# trashotron-driver.net
KiCad netlist of a schematic drawn in EAGLE
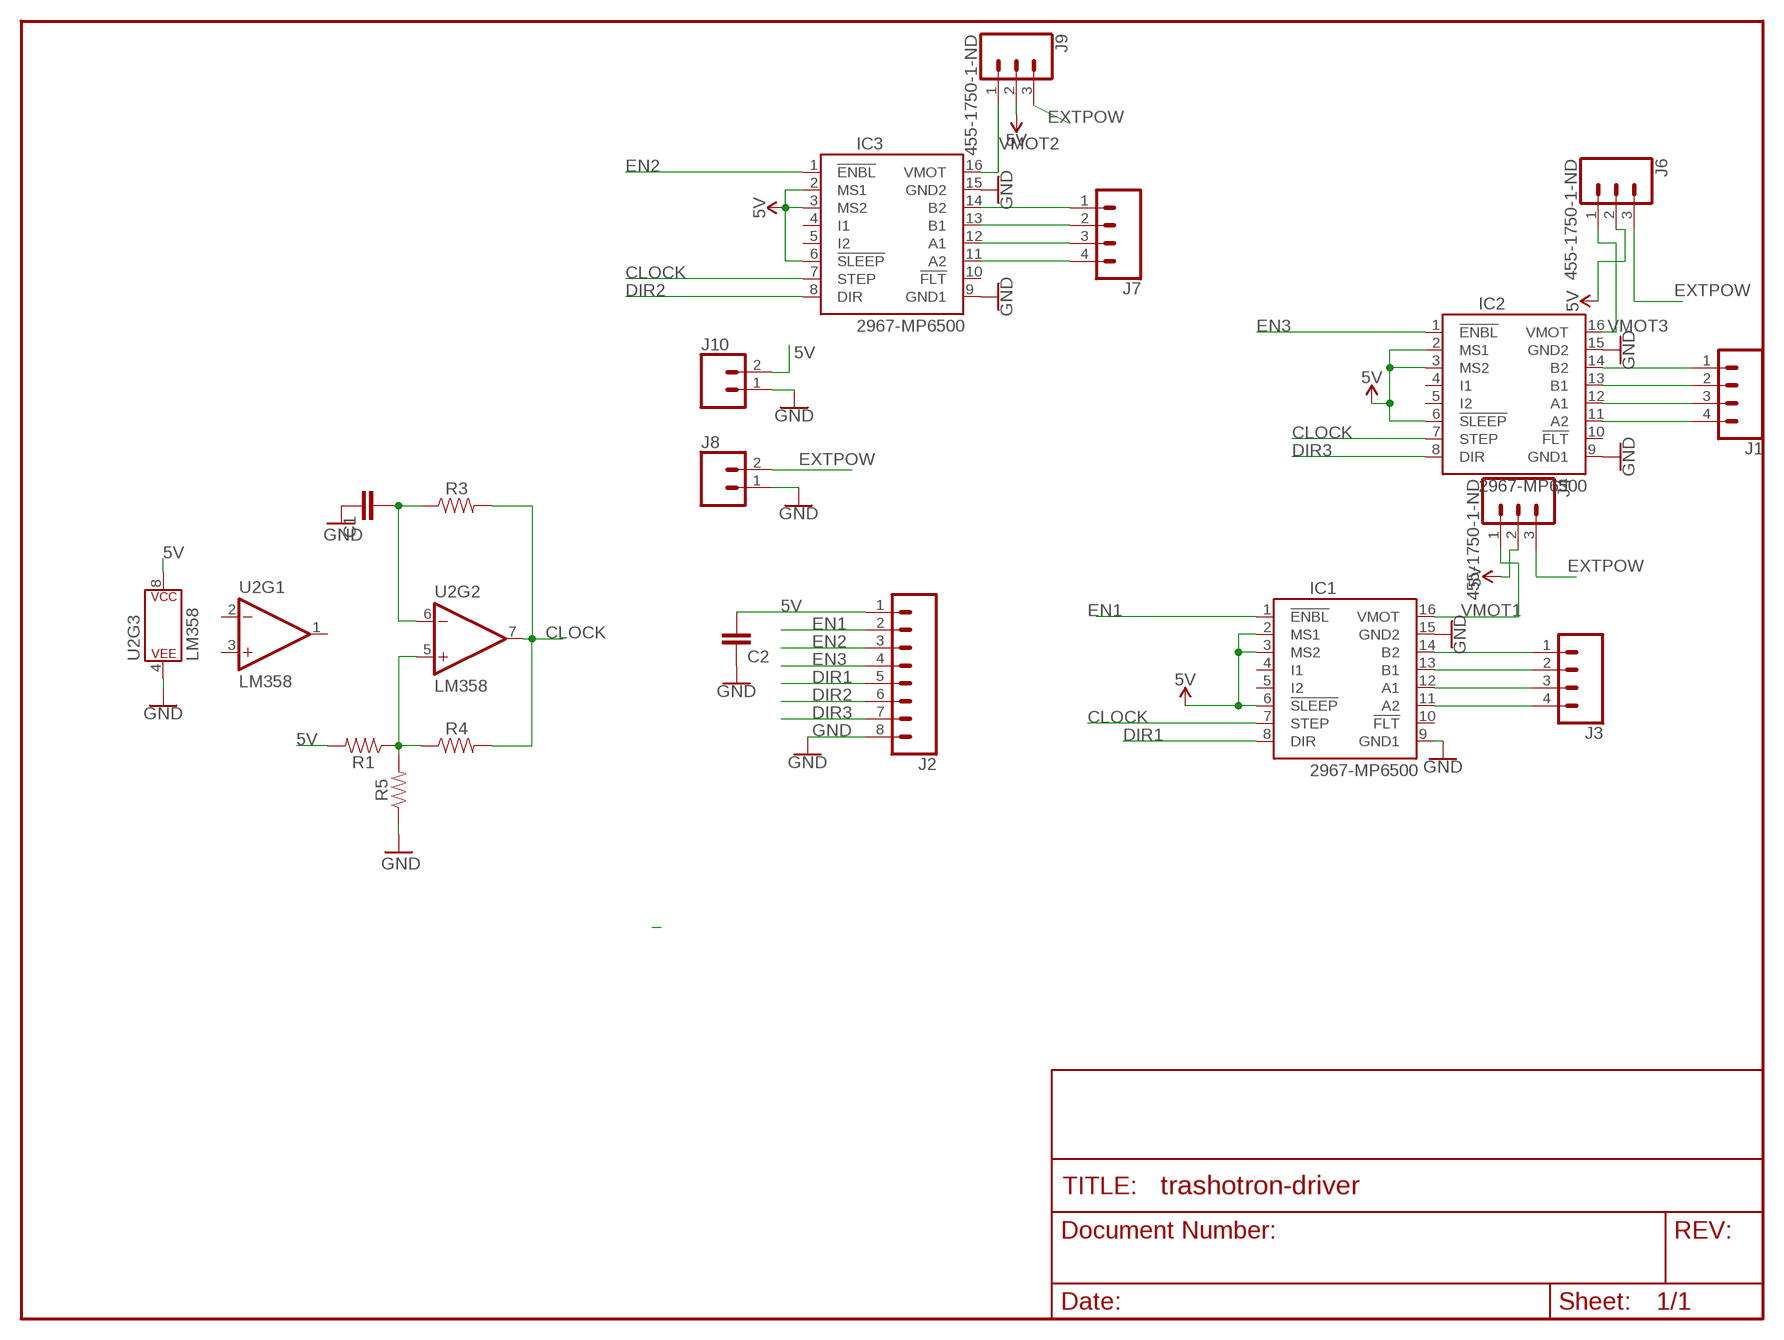
[diagram p0: schematic, sheet 1]

(export (version "E")
  (design (tool "Eeschema 10.0.6"))
  (components
    (comp (ref "C1")
      (value "C-EU050-050X075")
      (footprint "eagle-import:C050-050X075")
      (libsource (lib "eagle-import") (part "C-EU050-050X075"))
    )
    (comp (ref "C2")
      (value "C-EU050-050X075")
      (footprint "eagle-import:C050-050X075")
      (libsource (lib "eagle-import") (part "C-EU050-050X075"))
    )
    (comp (ref "IC1")
      (value "2967-MP6500")
      (footprint "eagle-import:MP6500")
      (libsource (lib "eagle-import") (part "2967-MP6500"))
    )
    (comp (ref "IC2")
      (value "2967-MP6500")
      (footprint "eagle-import:MP6500")
      (libsource (lib "eagle-import") (part "2967-MP6500"))
    )
    (comp (ref "IC3")
      (value "2967-MP6500")
      (footprint "eagle-import:MP6500")
      (libsource (lib "eagle-import") (part "2967-MP6500"))
    )
    (comp (ref "J1")
      (value "CONN_04")
      (footprint "eagle-import:1X04")
      (libsource (lib "eagle-import") (part "CONN_04"))
    )
    (comp (ref "J2")
      (value "CONN_08\"")
      (footprint "eagle-import:1X08")
      (libsource (lib "eagle-import") (part "CONN_08{dblquote}"))
    )
    (comp (ref "J3")
      (value "CONN_04")
      (footprint "eagle-import:1X04")
      (libsource (lib "eagle-import") (part "CONN_04"))
    )
    (comp (ref "J4")
      (value "455-1750-1-ND")
      (footprint "eagle-import:1X03")
      (libsource (lib "eagle-import") (part "CONN_03"))
    )
    (comp (ref "J6")
      (value "455-1750-1-ND")
      (footprint "eagle-import:1X03")
      (libsource (lib "eagle-import") (part "CONN_03"))
    )
    (comp (ref "J7")
      (value "CONN_04")
      (footprint "eagle-import:1X04")
      (libsource (lib "eagle-import") (part "CONN_04"))
    )
    (comp (ref "J8")
      (value "CONN_02")
      (footprint "eagle-import:1X02")
      (libsource (lib "eagle-import") (part "CONN_02"))
    )
    (comp (ref "J9")
      (value "455-1750-1-ND")
      (footprint "eagle-import:1X03")
      (libsource (lib "eagle-import") (part "CONN_03"))
    )
    (comp (ref "J10")
      (value "CONN_02")
      (footprint "eagle-import:1X02")
      (libsource (lib "eagle-import") (part "CONN_02"))
    )
    (comp (ref "R1")
      (value "RESISTORAXIAL-0.3")
      (footprint "eagle-import:AXIAL-0.3")
      (libsource (lib "eagle-import") (part "RESISTORAXIAL-0.3"))
    )
    (comp (ref "R3")
      (value "RESISTORAXIAL-0.3")
      (footprint "eagle-import:AXIAL-0.3")
      (libsource (lib "eagle-import") (part "RESISTORAXIAL-0.3"))
    )
    (comp (ref "R4")
      (value "RESISTORAXIAL-0.3")
      (footprint "eagle-import:AXIAL-0.3")
      (libsource (lib "eagle-import") (part "RESISTORAXIAL-0.3"))
    )
    (comp (ref "R5")
      (value "RESISTORAXIAL-0.3")
      (footprint "eagle-import:AXIAL-0.3")
      (libsource (lib "eagle-import") (part "RESISTORAXIAL-0.3"))
    )
    (comp (ref "U2")
      (value "LM358")
      (footprint "eagle-import:DIP08")
      (libsource (lib "eagle-import") (part "LM358"))
    )
  )
  (nets
    (net (code "1") (name "/CLOCK") (class "Default")
      (node (ref "IC1") (pin "7") (pinfunction "STEP_7") (pintype "input"))
      (node (ref "IC2") (pin "7") (pinfunction "STEP_7") (pintype "input"))
      (node (ref "IC3") (pin "7") (pinfunction "STEP_7") (pintype "input"))
      (node (ref "R3") (pin "P$2") (pinfunction "2_P$2") (pintype "passive"))
      (node (ref "R4") (pin "P$2") (pinfunction "2_P$2") (pintype "passive"))
      (node (ref "U2") (pin "7") (pinfunction "OUT_7") (pintype "output"))
    )
    (net (code "2") (name "/DIR1") (class "Default")
      (node (ref "IC1") (pin "8") (pinfunction "DIR_8") (pintype "input"))
      (node (ref "J2") (pin "5") (pinfunction "5_5") (pintype "passive"))
    )
    (net (code "3") (name "/DIR2") (class "Default")
      (node (ref "IC3") (pin "8") (pinfunction "DIR_8") (pintype "input"))
      (node (ref "J2") (pin "6") (pinfunction "6_6") (pintype "passive"))
    )
    (net (code "4") (name "/DIR3") (class "Default")
      (node (ref "IC2") (pin "8") (pinfunction "DIR_8") (pintype "input"))
      (node (ref "J2") (pin "7") (pinfunction "7_7") (pintype "passive"))
    )
    (net (code "5") (name "/EN1") (class "Default")
      (node (ref "IC1") (pin "1") (pinfunction "~{ENBL}_1") (pintype "passive"))
      (node (ref "J2") (pin "2") (pinfunction "2_2") (pintype "passive"))
    )
    (net (code "6") (name "/EN2") (class "Default")
      (node (ref "IC3") (pin "1") (pinfunction "~{ENBL}_1") (pintype "passive"))
      (node (ref "J2") (pin "3") (pinfunction "3_3") (pintype "passive"))
    )
    (net (code "7") (name "/EN3") (class "Default")
      (node (ref "IC2") (pin "1") (pinfunction "~{ENBL}_1") (pintype "passive"))
      (node (ref "J2") (pin "4") (pinfunction "4_4") (pintype "passive"))
    )
    (net (code "8") (name "/EXTPOW") (class "Default")
      (node (ref "J4") (pin "3") (pinfunction "3_3") (pintype "passive"))
      (node (ref "J6") (pin "3") (pinfunction "3_3") (pintype "passive"))
      (node (ref "J8") (pin "2") (pinfunction "2_2") (pintype "passive"))
      (node (ref "J9") (pin "3") (pinfunction "3_3") (pintype "passive"))
    )
    (net (code "9") (name "/VMOT1") (class "Default")
      (node (ref "IC1") (pin "16") (pinfunction "VMOT_16") (pintype "power_in"))
      (node (ref "J4") (pin "1") (pinfunction "1_1") (pintype "passive"))
    )
    (net (code "10") (name "/VMOT2") (class "Default")
      (node (ref "IC3") (pin "16") (pinfunction "VMOT_16") (pintype "power_in"))
      (node (ref "J9") (pin "1") (pinfunction "1_1") (pintype "passive"))
    )
    (net (code "11") (name "/VMOT3") (class "Default")
      (node (ref "IC2") (pin "16") (pinfunction "VMOT_16") (pintype "power_in"))
      (node (ref "J6") (pin "1") (pinfunction "1_1") (pintype "passive"))
    )
    (net (code "12") (name "5V") (class "Default")
      (node (ref "C2") (pin "2") (pinfunction "2_2") (pintype "passive"))
      (node (ref "IC1") (pin "2") (pinfunction "MS1_2") (pintype "passive"))
      (node (ref "IC1") (pin "3") (pinfunction "MS2_3") (pintype "passive"))
      (node (ref "IC1") (pin "6") (pinfunction "~{SLEEP}_6") (pintype "input"))
      (node (ref "IC2") (pin "2") (pinfunction "MS1_2") (pintype "passive"))
      (node (ref "IC2") (pin "3") (pinfunction "MS2_3") (pintype "passive"))
      (node (ref "IC2") (pin "6") (pinfunction "~{SLEEP}_6") (pintype "input"))
      (node (ref "IC3") (pin "2") (pinfunction "MS1_2") (pintype "passive"))
      (node (ref "IC3") (pin "3") (pinfunction "MS2_3") (pintype "passive"))
      (node (ref "IC3") (pin "6") (pinfunction "~{SLEEP}_6") (pintype "input"))
      (node (ref "J10") (pin "2") (pinfunction "2_2") (pintype "passive"))
      (node (ref "J2") (pin "1") (pinfunction "1_1") (pintype "passive"))
      (node (ref "J4") (pin "2") (pinfunction "2_2") (pintype "passive"))
      (node (ref "J6") (pin "2") (pinfunction "2_2") (pintype "passive"))
      (node (ref "J9") (pin "2") (pinfunction "2_2") (pintype "passive"))
      (node (ref "R1") (pin "P$2") (pinfunction "2_P$2") (pintype "passive"))
      (node (ref "U2") (pin "8") (pinfunction "P$V+_8") (pintype "bidirectional"))
    )
    (net (code "13") (name "GND") (class "Default")
      (node (ref "C1") (pin "1") (pinfunction "1_1") (pintype "passive"))
      (node (ref "C2") (pin "1") (pinfunction "1_1") (pintype "passive"))
      (node (ref "IC1") (pin "15") (pinfunction "GND2_15") (pintype "power_in"))
      (node (ref "IC1") (pin "9") (pinfunction "GND1_9") (pintype "power_in"))
      (node (ref "IC2") (pin "15") (pinfunction "GND2_15") (pintype "power_in"))
      (node (ref "IC2") (pin "9") (pinfunction "GND1_9") (pintype "power_in"))
      (node (ref "IC3") (pin "15") (pinfunction "GND2_15") (pintype "power_in"))
      (node (ref "IC3") (pin "9") (pinfunction "GND1_9") (pintype "power_in"))
      (node (ref "J10") (pin "1") (pinfunction "1_1") (pintype "passive"))
      (node (ref "J2") (pin "8") (pinfunction "8_8") (pintype "passive"))
      (node (ref "J8") (pin "1") (pinfunction "1_1") (pintype "passive"))
      (node (ref "R5") (pin "P$1") (pinfunction "1_P$1") (pintype "passive"))
      (node (ref "U2") (pin "4") (pinfunction "P$V-_4") (pintype "bidirectional"))
    )
    (net (code "14") (name "Net-(IC1-A1)") (class "Default")
      (node (ref "IC1") (pin "12") (pinfunction "A1_12") (pintype "output"))
      (node (ref "J3") (pin "3") (pinfunction "3_3") (pintype "passive"))
    )
    (net (code "15") (name "Net-(IC1-A2)") (class "Default")
      (node (ref "IC1") (pin "11") (pinfunction "A2_11") (pintype "output"))
      (node (ref "J3") (pin "4") (pinfunction "4_4") (pintype "passive"))
    )
    (net (code "16") (name "Net-(IC1-B1)") (class "Default")
      (node (ref "IC1") (pin "13") (pinfunction "B1_13") (pintype "output"))
      (node (ref "J3") (pin "2") (pinfunction "2_2") (pintype "passive"))
    )
    (net (code "17") (name "Net-(IC1-B2)") (class "Default")
      (node (ref "IC1") (pin "14") (pinfunction "B2_14") (pintype "output"))
      (node (ref "J3") (pin "1") (pinfunction "1_1") (pintype "passive"))
    )
    (net (code "18") (name "Net-(IC2-A1)") (class "Default")
      (node (ref "IC2") (pin "12") (pinfunction "A1_12") (pintype "output"))
      (node (ref "J1") (pin "3") (pinfunction "3_3") (pintype "passive"))
    )
    (net (code "19") (name "Net-(IC2-A2)") (class "Default")
      (node (ref "IC2") (pin "11") (pinfunction "A2_11") (pintype "output"))
      (node (ref "J1") (pin "4") (pinfunction "4_4") (pintype "passive"))
    )
    (net (code "20") (name "Net-(IC2-B1)") (class "Default")
      (node (ref "IC2") (pin "13") (pinfunction "B1_13") (pintype "output"))
      (node (ref "J1") (pin "2") (pinfunction "2_2") (pintype "passive"))
    )
    (net (code "21") (name "Net-(IC2-B2)") (class "Default")
      (node (ref "IC2") (pin "14") (pinfunction "B2_14") (pintype "output"))
      (node (ref "J1") (pin "1") (pinfunction "1_1") (pintype "passive"))
    )
    (net (code "22") (name "Net-(IC3-A1)") (class "Default")
      (node (ref "IC3") (pin "12") (pinfunction "A1_12") (pintype "output"))
      (node (ref "J7") (pin "3") (pinfunction "3_3") (pintype "passive"))
    )
    (net (code "23") (name "Net-(IC3-A2)") (class "Default")
      (node (ref "IC3") (pin "11") (pinfunction "A2_11") (pintype "output"))
      (node (ref "J7") (pin "4") (pinfunction "4_4") (pintype "passive"))
    )
    (net (code "24") (name "Net-(IC3-B1)") (class "Default")
      (node (ref "IC3") (pin "13") (pinfunction "B1_13") (pintype "output"))
      (node (ref "J7") (pin "2") (pinfunction "2_2") (pintype "passive"))
    )
    (net (code "25") (name "Net-(IC3-B2)") (class "Default")
      (node (ref "IC3") (pin "14") (pinfunction "B2_14") (pintype "output"))
      (node (ref "J7") (pin "1") (pinfunction "1_1") (pintype "passive"))
    )
    (net (code "26") (name "Net-(R1-1)") (class "Default")
      (node (ref "R1") (pin "P$1") (pinfunction "1_P$1") (pintype "passive"))
      (node (ref "R4") (pin "P$1") (pinfunction "1_P$1") (pintype "passive"))
      (node (ref "R5") (pin "P$2") (pinfunction "2_P$2") (pintype "passive"))
      (node (ref "U2") (pin "5") (pinfunction "+IN_5") (pintype "input"))
    )
    (net (code "27") (name "Net-(R3-1)") (class "Default")
      (node (ref "C1") (pin "2") (pinfunction "2_2") (pintype "passive"))
      (node (ref "R3") (pin "P$1") (pinfunction "1_P$1") (pintype "passive"))
      (node (ref "U2") (pin "6") (pinfunction "-IN_6") (pintype "input"))
    )
    (net (code "28") (name "unconnected-(IC1-I1-Pad4)") (class "Default")
      (node (ref "IC1") (pin "4") (pinfunction "I1_4") (pintype "passive"))
    )
    (net (code "29") (name "unconnected-(IC1-I2-Pad5)") (class "Default")
      (node (ref "IC1") (pin "5") (pinfunction "I2_5") (pintype "passive"))
    )
    (net (code "30") (name "unconnected-(IC1-~{FLT}-Pad10)") (class "Default")
      (node (ref "IC1") (pin "10") (pinfunction "~{FLT}_10") (pintype "open_collector"))
    )
    (net (code "31") (name "unconnected-(IC2-I1-Pad4)") (class "Default")
      (node (ref "IC2") (pin "4") (pinfunction "I1_4") (pintype "passive"))
    )
    (net (code "32") (name "unconnected-(IC2-I2-Pad5)") (class "Default")
      (node (ref "IC2") (pin "5") (pinfunction "I2_5") (pintype "passive"))
    )
    (net (code "33") (name "unconnected-(IC2-~{FLT}-Pad10)") (class "Default")
      (node (ref "IC2") (pin "10") (pinfunction "~{FLT}_10") (pintype "open_collector"))
    )
    (net (code "34") (name "unconnected-(IC3-I1-Pad4)") (class "Default")
      (node (ref "IC3") (pin "4") (pinfunction "I1_4") (pintype "passive"))
    )
    (net (code "35") (name "unconnected-(IC3-I2-Pad5)") (class "Default")
      (node (ref "IC3") (pin "5") (pinfunction "I2_5") (pintype "passive"))
    )
    (net (code "36") (name "unconnected-(IC3-~{FLT}-Pad10)") (class "Default")
      (node (ref "IC3") (pin "10") (pinfunction "~{FLT}_10") (pintype "open_collector"))
    )
    (net (code "37") (name "unconnected-(U2A-+IN-Pad3)") (class "Default")
      (node (ref "U2") (pin "3") (pinfunction "+IN_3") (pintype "input"))
    )
    (net (code "38") (name "unconnected-(U2A--IN-Pad2)") (class "Default")
      (node (ref "U2") (pin "2") (pinfunction "-IN_2") (pintype "input"))
    )
    (net (code "39") (name "unconnected-(U2A-OUT-Pad1)") (class "Default")
      (node (ref "U2") (pin "1") (pinfunction "OUT_1") (pintype "output"))
    )
  )
)
